# ProPrj_can_sniffer_2026-02-20.net
KiCad netlist of a schematic drawn in EasyEDA Pro
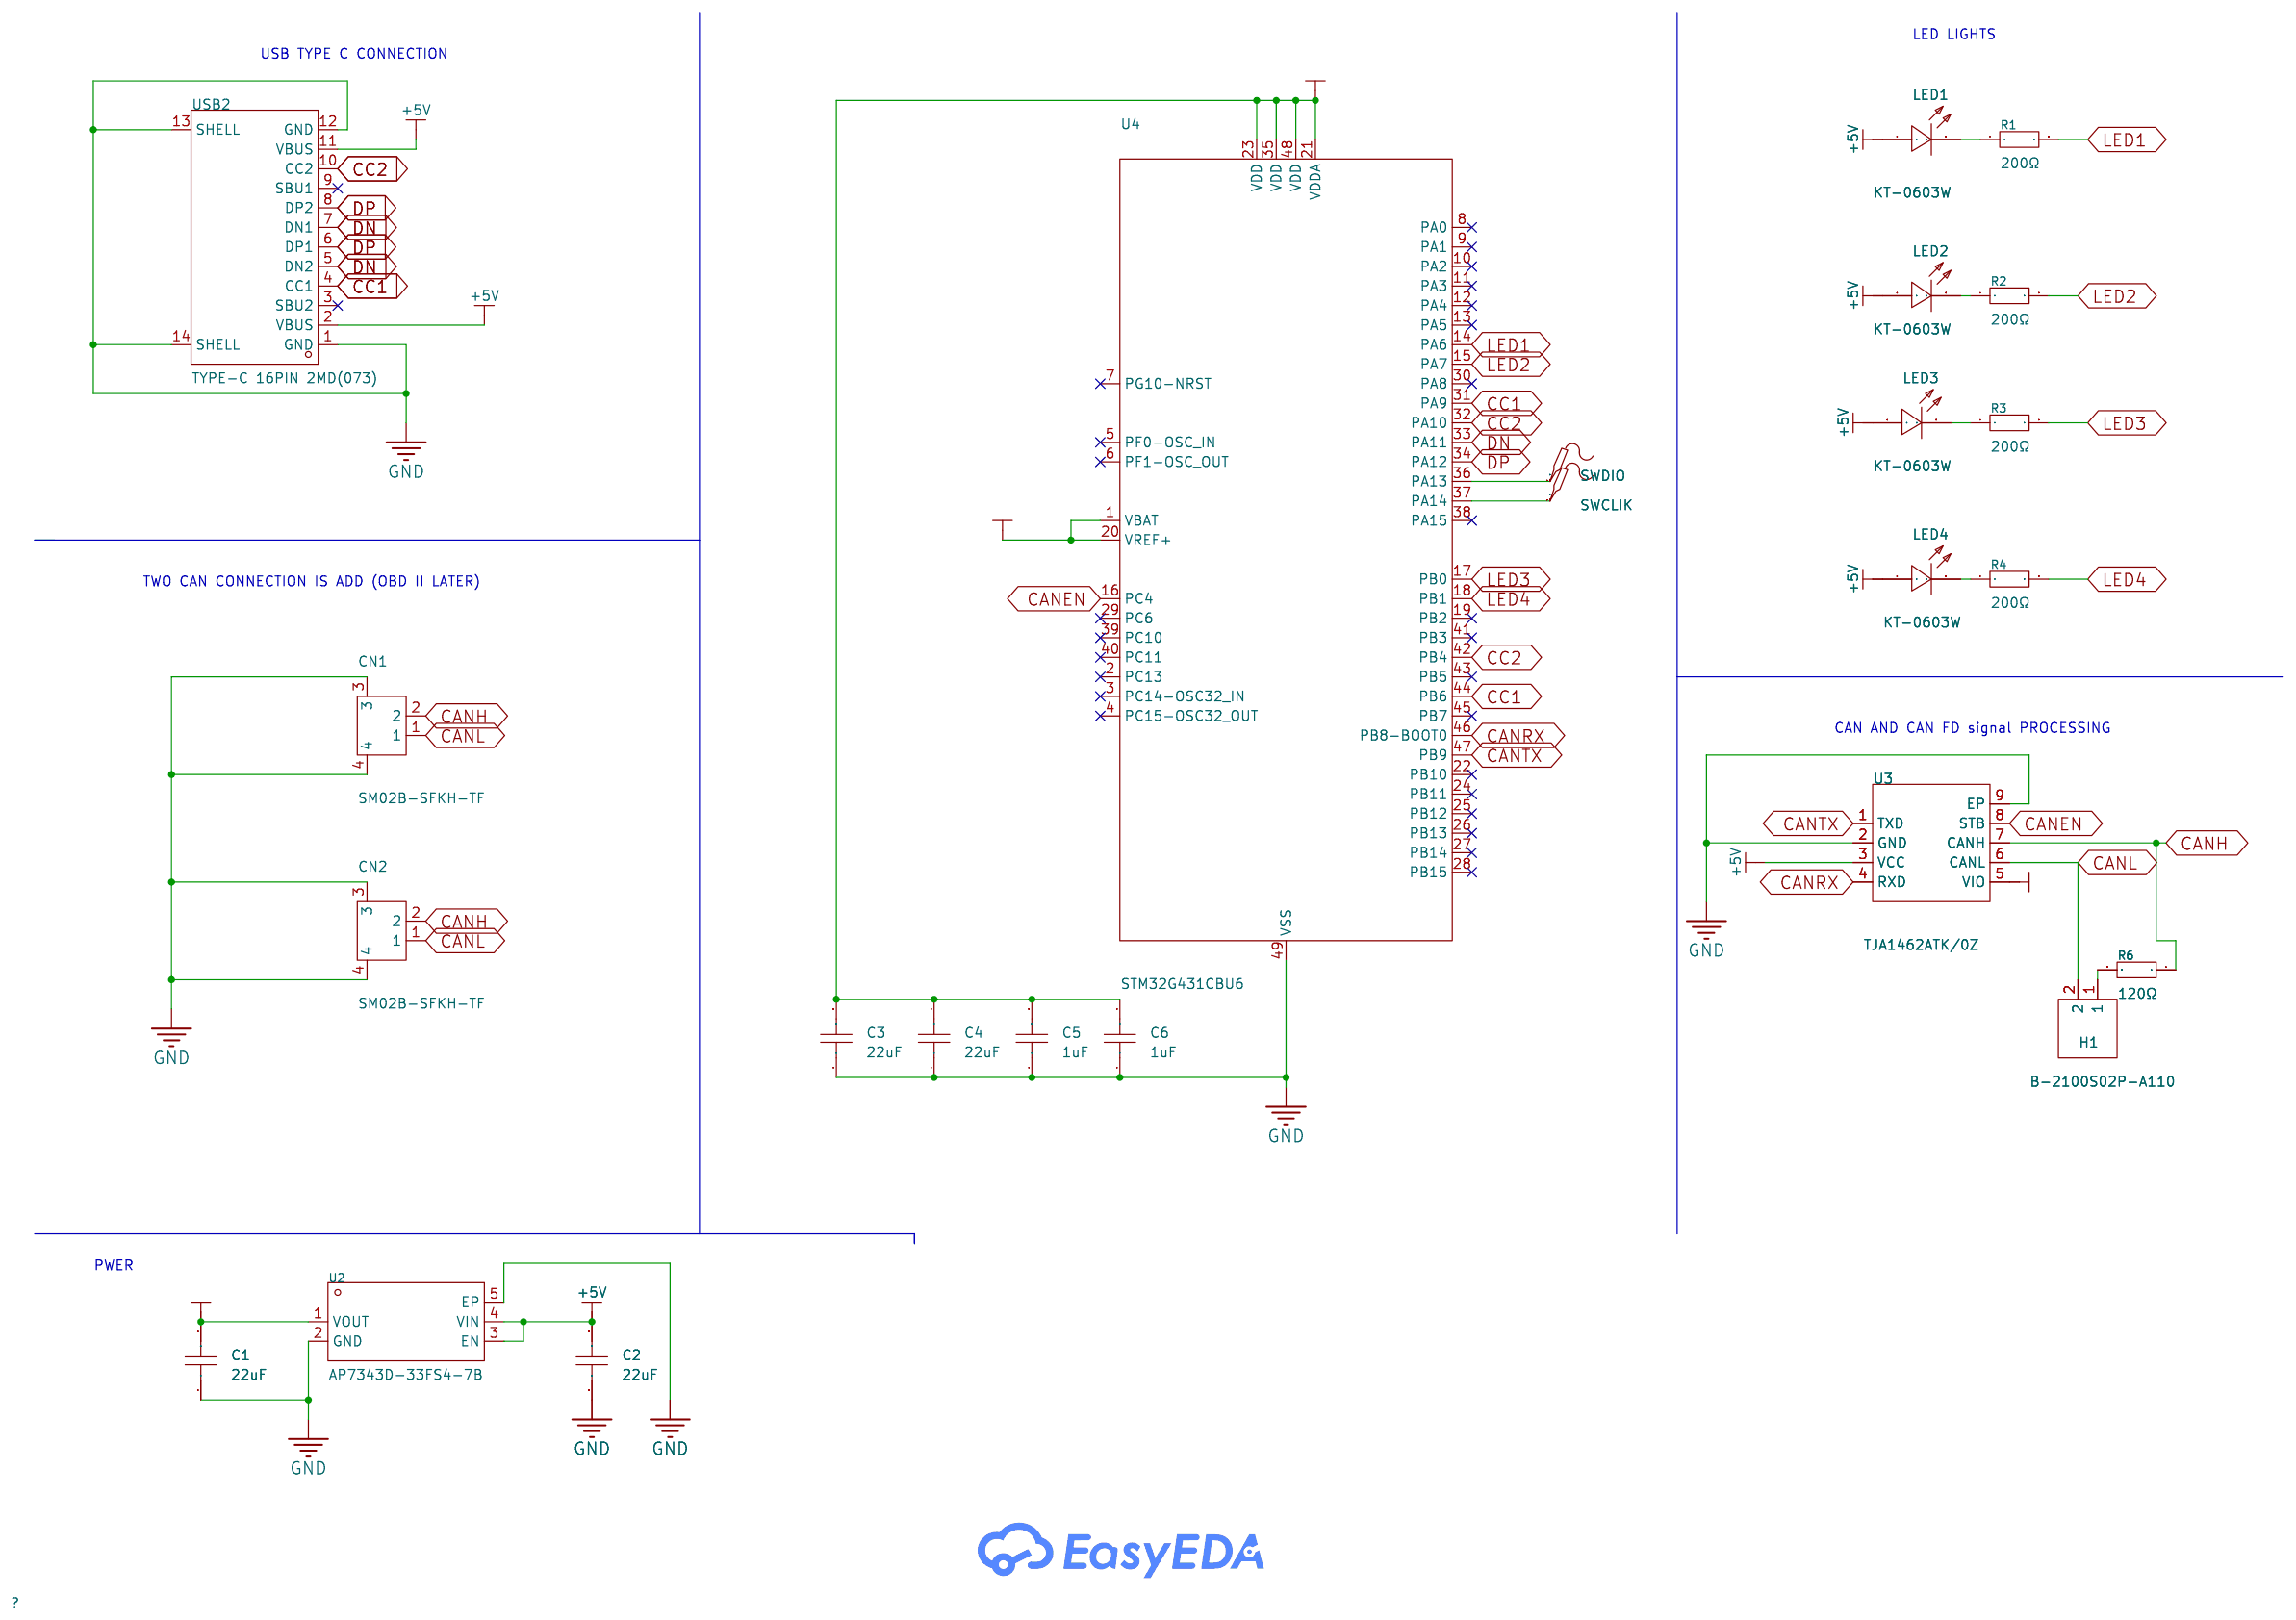
[diagram p0: schematic sheet]

(export (version "E")
  (design (tool "Eeschema 10.0.6"))
  (components
    (comp (ref "C1")
      (value "22uF")
      (footprint "easyedapro:C0603")
      (description "Capacitance:22uF Tolerance:±20% Tolerance:±20% Voltage Rating:6.3V Temperature Coefficient:X5R")
      (fields
        (field (name "Manufacturer Part") "CL10A226MQ8NRNC")
        (field (name "Manufacturer") "SAMSUNG(三星)")
      )
      (libsource (lib "easyedapro") (part "CL10A226MQ8NRNC"))
    )
    (comp (ref "C2")
      (value "22uF")
      (footprint "easyedapro:C0603")
      (description "Capacitance:22uF Tolerance:±20% Tolerance:±20% Voltage Rating:6.3V Temperature Coefficient:X5R")
      (fields
        (field (name "Manufacturer Part") "CL10A226MQ8NRNC")
        (field (name "Manufacturer") "SAMSUNG(三星)")
      )
      (libsource (lib "easyedapro") (part "CL10A226MQ8NRNC"))
    )
    (comp (ref "C3")
      (value "22uF")
      (footprint "easyedapro:C0603")
      (description "Capacitance:22uF Tolerance:±20% Tolerance:±20% Voltage Rating:6.3V Temperature Coefficient:X5R")
      (fields
        (field (name "Manufacturer Part") "CL10A226MQ8NRNC")
        (field (name "Manufacturer") "SAMSUNG(三星)")
      )
      (libsource (lib "easyedapro") (part "CL10A226MQ8NRNC"))
    )
    (comp (ref "C4")
      (value "22uF")
      (footprint "easyedapro:C0603")
      (description "Capacitance:22uF Tolerance:±20% Tolerance:±20% Voltage Rating:6.3V Temperature Coefficient:X5R")
      (fields
        (field (name "Manufacturer Part") "CL10A226MQ8NRNC")
        (field (name "Manufacturer") "SAMSUNG(三星)")
      )
      (libsource (lib "easyedapro") (part "CL10A226MQ8NRNC"))
    )
    (comp (ref "C5")
      (value "1uF")
      (footprint "easyedapro:C0402")
      (description "Capacitance:1uF Tolerance:±10% Tolerance:±10% Voltage Rating:25V Temperature Coefficient:X5R")
      (fields
        (field (name "Manufacturer Part") "CL05A105KA5NQNC")
        (field (name "Manufacturer") "SAMSUNG(三星)")
      )
      (libsource (lib "easyedapro") (part "CL05A105KA5NQNC"))
    )
    (comp (ref "C6")
      (value "1uF")
      (footprint "easyedapro:C0402")
      (description "Capacitance:1uF Tolerance:±10% Tolerance:±10% Voltage Rating:25V Temperature Coefficient:X5R")
      (fields
        (field (name "Manufacturer Part") "CL05A105KA5NQNC")
        (field (name "Manufacturer") "SAMSUNG(三星)")
      )
      (libsource (lib "easyedapro") (part "CL05A105KA5NQNC"))
    )
    (comp (ref "CN1")
      (value "SM02B-SFKH-TF")
      (footprint "easyedapro:CONN-SMD_SM02B-SFKH-TF")
      (fields (field (name "Manufacturer") "JST"))
      (libsource (lib "easyedapro") (part "SM02B-SFKH-TF"))
    )
    (comp (ref "CN2")
      (value "SM02B-SFKH-TF")
      (footprint "easyedapro:CONN-SMD_SM02B-SFKH-TF")
      (fields (field (name "Manufacturer") "JST"))
      (libsource (lib "easyedapro") (part "SM02B-SFKH-TF"))
    )
    (comp (ref "H1")
      (value "B-2100S02P-A110")
      (footprint "easyedapro:HDR-TH_2P-P2.54-V-M-1")
      (fields (field (name "Manufacturer") "Ckmtw(灿科盟)"))
      (libsource (lib "easyedapro") (part "210S-1*2P L=11.6MMGold-plated black"))
    )
    (comp (ref "LED1")
      (value "KT-0603W")
      (footprint "easyedapro:LED0603-R-RD_WHITE")
      (fields (field (name "Manufacturer") "KENTO"))
      (libsource (lib "easyedapro") (part "0603White light_C2290"))
    )
    (comp (ref "LED2")
      (value "KT-0603W")
      (footprint "easyedapro:LED0603-R-RD_WHITE")
      (fields (field (name "Manufacturer") "KENTO"))
      (libsource (lib "easyedapro") (part "0603White light_C2290"))
    )
    (comp (ref "LED3")
      (value "KT-0603W")
      (footprint "easyedapro:LED0603-R-RD_WHITE")
      (fields (field (name "Manufacturer") "KENTO"))
      (libsource (lib "easyedapro") (part "0603White light_C2290"))
    )
    (comp (ref "LED4")
      (value "KT-0603W")
      (footprint "easyedapro:LED0603-R-RD_WHITE")
      (fields (field (name "Manufacturer") "KENTO"))
      (libsource (lib "easyedapro") (part "0603White light_C2290"))
    )
    (comp (ref "R1")
      (value "200Ω")
      (footprint "easyedapro:R0402")
      (fields
        (field (name "Manufacturer Part") "0402WGF2000TCE")
        (field (name "Manufacturer") "UNI-ROYAL(厚声)")
      )
      (libsource (lib "easyedapro") (part "0402WGF2000TCE"))
    )
    (comp (ref "R2")
      (value "200Ω")
      (footprint "easyedapro:R0402")
      (fields
        (field (name "Manufacturer Part") "0402WGF2000TCE")
        (field (name "Manufacturer") "UNI-ROYAL(厚声)")
      )
      (libsource (lib "easyedapro") (part "0402WGF2000TCE"))
    )
    (comp (ref "R3")
      (value "200Ω")
      (footprint "easyedapro:R0402")
      (fields
        (field (name "Manufacturer Part") "0402WGF2000TCE")
        (field (name "Manufacturer") "UNI-ROYAL(厚声)")
      )
      (libsource (lib "easyedapro") (part "0402WGF2000TCE"))
    )
    (comp (ref "R4")
      (value "200Ω")
      (footprint "easyedapro:R0402")
      (fields
        (field (name "Manufacturer Part") "0402WGF2000TCE")
        (field (name "Manufacturer") "UNI-ROYAL(厚声)")
      )
      (libsource (lib "easyedapro") (part "0402WGF2000TCE"))
    )
    (comp (ref "R6")
      (value "120Ω")
      (footprint "easyedapro:R0603")
      (fields
        (field (name "Manufacturer Part") "0603WAF1200T5E")
        (field (name "Manufacturer") "UNI-ROYAL(厚声)")
      )
      (libsource (lib "easyedapro") (part "0603WAF1200T5E"))
    )
    (comp (ref "SWCLIK")
      (value "~")
      (footprint "easyedapro:Test-Point-0.5mm")
      (description "Test Point 测试点")
      (libsource (lib "easyedapro") (part "Test-Point"))
    )
    (comp (ref "SWDIO")
      (value "~")
      (footprint "easyedapro:Test-Point-0.5mm")
      (description "Test Point 测试点")
      (libsource (lib "easyedapro") (part "Test-Point"))
    )
    (comp (ref "U2")
      (value "AP7343D-33FS4-7B")
      (footprint "easyedapro:DFN-4_L1.0-W1.0-P0.65-BL-EP")
      (fields (field (name "Manufacturer") "DIODES(美台)"))
      (libsource (lib "easyedapro") (part "AP7343D-33FS4-7B"))
    )
    (comp (ref "U3")
      (value "TJA1462ATK/0Z")
      (footprint "easyedapro:HVSON-8_L3.0-W3.0-P0.65-TL-EP")
      (fields (field (name "Manufacturer") "NXP(恩智浦)"))
      (libsource (lib "easyedapro") (part "TJA1462ATK/0Z"))
    )
    (comp (ref "U4")
      (value "STM32G431CBU6")
      (footprint "easyedapro:VQFN-48_L7.0-W7.0-P0.50-BL-EP5.5")
      (fields (field (name "Manufacturer") "ST(意法半导体)"))
      (libsource (lib "easyedapro") (part "STM32G431CBU6"))
    )
    (comp (ref "USB2")
      (value "TYPE-C 16PIN 2MD(073)")
      (footprint "easyedapro:USB-C-SMD_TYPE-C-6PIN-2MD-073")
      (fields (field (name "Manufacturer") "SHOU HAN(首韩)"))
      (libsource (lib "easyedapro") (part "TYPE-C 16PIN 2MD(073)"))
    )
  )
  (nets
    (net (code "1") (name "+5V") (class "Default")
      (node (ref "C2") (pin "2") (pinfunction "2_2") (pintype "unspecified"))
      (node (ref "LED1") (pin "1") (pinfunction "A_1") (pintype "unspecified"))
      (node (ref "LED2") (pin "1") (pinfunction "A_1") (pintype "unspecified"))
      (node (ref "LED3") (pin "1") (pinfunction "A_1") (pintype "unspecified"))
      (node (ref "LED4") (pin "1") (pinfunction "A_1") (pintype "unspecified"))
      (node (ref "U2") (pin "3") (pinfunction "EN_3") (pintype "input"))
      (node (ref "U2") (pin "4") (pinfunction "VIN_4") (pintype "input"))
      (node (ref "U3") (pin "3") (pinfunction "VCC_3") (pintype "unspecified"))
      (node (ref "USB2") (pin "11") (pinfunction "VBUS_11") (pintype "unspecified"))
      (node (ref "USB2") (pin "2") (pinfunction "VBUS_2") (pintype "unspecified"))
    )
    (net (code "2") (name "3V3") (class "Default")
      (node (ref "C1") (pin "2") (pinfunction "2_2") (pintype "unspecified"))
      (node (ref "C3") (pin "2") (pinfunction "2_2") (pintype "unspecified"))
      (node (ref "C4") (pin "2") (pinfunction "2_2") (pintype "unspecified"))
      (node (ref "C5") (pin "2") (pinfunction "2_2") (pintype "unspecified"))
      (node (ref "C6") (pin "2") (pinfunction "2_2") (pintype "unspecified"))
      (node (ref "U2") (pin "1") (pinfunction "VOUT_1") (pintype "input"))
      (node (ref "U3") (pin "5") (pinfunction "VIO_5") (pintype "unspecified"))
      (node (ref "U4") (pin "1") (pinfunction "VBAT_1") (pintype "unspecified"))
      (node (ref "U4") (pin "20") (pinfunction "VREF+_20") (pintype "unspecified"))
      (node (ref "U4") (pin "21") (pinfunction "VDDA_21") (pintype "unspecified"))
      (node (ref "U4") (pin "23") (pinfunction "VDD_23") (pintype "unspecified"))
      (node (ref "U4") (pin "35") (pinfunction "VDD_35") (pintype "unspecified"))
      (node (ref "U4") (pin "48") (pinfunction "VDD_48") (pintype "unspecified"))
    )
    (net (code "3") (name "CANEN") (class "Default")
      (node (ref "U3") (pin "8") (pinfunction "STB_8") (pintype "unspecified"))
      (node (ref "U4") (pin "16") (pinfunction "PC4_16") (pintype "unspecified"))
    )
    (net (code "4") (name "CANH") (class "Default")
      (node (ref "CN1") (pin "2") (pinfunction "2_2") (pintype "unspecified"))
      (node (ref "CN2") (pin "2") (pinfunction "2_2") (pintype "unspecified"))
      (node (ref "R6") (pin "1") (pinfunction "1_1") (pintype "input"))
      (node (ref "U3") (pin "7") (pinfunction "CANH_7") (pintype "unspecified"))
    )
    (net (code "5") (name "CANL") (class "Default")
      (node (ref "CN1") (pin "1") (pinfunction "1_1") (pintype "unspecified"))
      (node (ref "CN2") (pin "1") (pinfunction "1_1") (pintype "unspecified"))
      (node (ref "H1") (pin "2") (pinfunction "2_2") (pintype "unspecified"))
      (node (ref "U3") (pin "6") (pinfunction "CANL_6") (pintype "unspecified"))
    )
    (net (code "6") (name "CANRX") (class "Default")
      (node (ref "U3") (pin "4") (pinfunction "RXD_4") (pintype "unspecified"))
      (node (ref "U4") (pin "46") (pinfunction "PB8-BOOT0_46") (pintype "unspecified"))
    )
    (net (code "7") (name "CANTX") (class "Default")
      (node (ref "U3") (pin "1") (pinfunction "TXD_1") (pintype "unspecified"))
      (node (ref "U4") (pin "47") (pinfunction "PB9_47") (pintype "unspecified"))
    )
    (net (code "8") (name "CC1") (class "Default")
      (node (ref "U4") (pin "31") (pinfunction "PA9_31") (pintype "unspecified"))
      (node (ref "U4") (pin "44") (pinfunction "PB6_44") (pintype "unspecified"))
      (node (ref "USB2") (pin "4") (pinfunction "CC1_4") (pintype "unspecified"))
    )
    (net (code "9") (name "CC2") (class "Default")
      (node (ref "U4") (pin "32") (pinfunction "PA10_32") (pintype "unspecified"))
      (node (ref "U4") (pin "42") (pinfunction "PB4_42") (pintype "unspecified"))
      (node (ref "USB2") (pin "10") (pinfunction "CC2_10") (pintype "unspecified"))
    )
    (net (code "10") (name "DN") (class "Default")
      (node (ref "U4") (pin "33") (pinfunction "PA11_33") (pintype "unspecified"))
      (node (ref "USB2") (pin "5") (pinfunction "DN2_5") (pintype "unspecified"))
      (node (ref "USB2") (pin "7") (pinfunction "DN1_7") (pintype "unspecified"))
    )
    (net (code "11") (name "DP") (class "Default")
      (node (ref "U4") (pin "34") (pinfunction "PA12_34") (pintype "unspecified"))
      (node (ref "USB2") (pin "6") (pinfunction "DP1_6") (pintype "unspecified"))
      (node (ref "USB2") (pin "8") (pinfunction "DP2_8") (pintype "unspecified"))
    )
    (net (code "12") (name "GND") (class "Default")
      (node (ref "C1") (pin "1") (pinfunction "1_1") (pintype "unspecified"))
      (node (ref "C2") (pin "1") (pinfunction "1_1") (pintype "unspecified"))
      (node (ref "C3") (pin "1") (pinfunction "1_1") (pintype "unspecified"))
      (node (ref "C4") (pin "1") (pinfunction "1_1") (pintype "unspecified"))
      (node (ref "C5") (pin "1") (pinfunction "1_1") (pintype "unspecified"))
      (node (ref "C6") (pin "1") (pinfunction "1_1") (pintype "unspecified"))
      (node (ref "CN1") (pin "3") (pinfunction "3_3") (pintype "unspecified"))
      (node (ref "CN1") (pin "4") (pinfunction "4_4") (pintype "unspecified"))
      (node (ref "CN2") (pin "3") (pinfunction "3_3") (pintype "unspecified"))
      (node (ref "CN2") (pin "4") (pinfunction "4_4") (pintype "unspecified"))
      (node (ref "U2") (pin "2") (pinfunction "GND_2") (pintype "input"))
      (node (ref "U2") (pin "5") (pinfunction "EP_5") (pintype "input"))
      (node (ref "U3") (pin "2") (pinfunction "GND_2") (pintype "unspecified"))
      (node (ref "U3") (pin "9") (pinfunction "EP_9") (pintype "unspecified"))
      (node (ref "U4") (pin "49") (pinfunction "VSS_49") (pintype "unspecified"))
      (node (ref "USB2") (pin "1") (pinfunction "GND_1") (pintype "unspecified"))
      (node (ref "USB2") (pin "12") (pinfunction "GND_12") (pintype "unspecified"))
      (node (ref "USB2") (pin "13") (pinfunction "SHELL_13") (pintype "unspecified"))
      (node (ref "USB2") (pin "14") (pinfunction "SHELL_14") (pintype "unspecified"))
    )
    (net (code "13") (name "LED1") (class "Default")
      (node (ref "R1") (pin "2") (pinfunction "2_2") (pintype "input"))
      (node (ref "U4") (pin "14") (pinfunction "PA6_14") (pintype "unspecified"))
    )
    (net (code "14") (name "LED2") (class "Default")
      (node (ref "R2") (pin "2") (pinfunction "2_2") (pintype "input"))
      (node (ref "U4") (pin "15") (pinfunction "PA7_15") (pintype "unspecified"))
    )
    (net (code "15") (name "LED3") (class "Default")
      (node (ref "R3") (pin "2") (pinfunction "2_2") (pintype "input"))
      (node (ref "U4") (pin "17") (pinfunction "PB0_17") (pintype "unspecified"))
    )
    (net (code "16") (name "LED4") (class "Default")
      (node (ref "R4") (pin "2") (pinfunction "2_2") (pintype "input"))
      (node (ref "U4") (pin "18") (pinfunction "PB1_18") (pintype "unspecified"))
    )
    (net (code "17") (name "Net-(H1-Pad1)") (class "Default")
      (node (ref "H1") (pin "1") (pinfunction "1_1") (pintype "unspecified"))
      (node (ref "R6") (pin "2") (pinfunction "2_2") (pintype "input"))
    )
    (net (code "18") (name "Net-(LED1-K)") (class "Default")
      (node (ref "LED1") (pin "2") (pinfunction "K_2") (pintype "unspecified"))
      (node (ref "R1") (pin "1") (pinfunction "1_1") (pintype "input"))
    )
    (net (code "19") (name "Net-(LED2-K)") (class "Default")
      (node (ref "LED2") (pin "2") (pinfunction "K_2") (pintype "unspecified"))
      (node (ref "R2") (pin "1") (pinfunction "1_1") (pintype "input"))
    )
    (net (code "20") (name "Net-(LED3-K)") (class "Default")
      (node (ref "LED3") (pin "2") (pinfunction "K_2") (pintype "unspecified"))
      (node (ref "R3") (pin "1") (pinfunction "1_1") (pintype "input"))
    )
    (net (code "21") (name "Net-(LED4-K)") (class "Default")
      (node (ref "LED4") (pin "2") (pinfunction "K_2") (pintype "unspecified"))
      (node (ref "R4") (pin "1") (pinfunction "1_1") (pintype "input"))
    )
    (net (code "22") (name "Net-(U4-PA13)") (class "Default")
      (node (ref "SWDIO") (pin "1") (pinfunction "1_1") (pintype "unspecified"))
      (node (ref "U4") (pin "36") (pinfunction "PA13_36") (pintype "unspecified"))
    )
    (net (code "23") (name "Net-(U4-PA14)") (class "Default")
      (node (ref "SWCLIK") (pin "1") (pinfunction "1_1") (pintype "unspecified"))
      (node (ref "U4") (pin "37") (pinfunction "PA14_37") (pintype "unspecified"))
    )
    (net (code "24") (name "unconnected-(U4-PA0-Pad8)") (class "Default")
      (node (ref "U4") (pin "8") (pinfunction "PA0_8") (pintype "unspecified+no_connect"))
    )
    (net (code "25") (name "unconnected-(U4-PA1-Pad9)") (class "Default")
      (node (ref "U4") (pin "9") (pinfunction "PA1_9") (pintype "unspecified+no_connect"))
    )
    (net (code "26") (name "unconnected-(U4-PA2-Pad10)") (class "Default")
      (node (ref "U4") (pin "10") (pinfunction "PA2_10") (pintype "unspecified+no_connect"))
    )
    (net (code "27") (name "unconnected-(U4-PA3-Pad11)") (class "Default")
      (node (ref "U4") (pin "11") (pinfunction "PA3_11") (pintype "unspecified+no_connect"))
    )
    (net (code "28") (name "unconnected-(U4-PA4-Pad12)") (class "Default")
      (node (ref "U4") (pin "12") (pinfunction "PA4_12") (pintype "unspecified+no_connect"))
    )
    (net (code "29") (name "unconnected-(U4-PA5-Pad13)") (class "Default")
      (node (ref "U4") (pin "13") (pinfunction "PA5_13") (pintype "unspecified+no_connect"))
    )
    (net (code "30") (name "unconnected-(U4-PA8-Pad30)") (class "Default")
      (node (ref "U4") (pin "30") (pinfunction "PA8_30") (pintype "unspecified+no_connect"))
    )
    (net (code "31") (name "unconnected-(U4-PA15-Pad38)") (class "Default")
      (node (ref "U4") (pin "38") (pinfunction "PA15_38") (pintype "unspecified+no_connect"))
    )
    (net (code "32") (name "unconnected-(U4-PB2-Pad19)") (class "Default")
      (node (ref "U4") (pin "19") (pinfunction "PB2_19") (pintype "unspecified+no_connect"))
    )
    (net (code "33") (name "unconnected-(U4-PB3-Pad41)") (class "Default")
      (node (ref "U4") (pin "41") (pinfunction "PB3_41") (pintype "unspecified+no_connect"))
    )
    (net (code "34") (name "unconnected-(U4-PB5-Pad43)") (class "Default")
      (node (ref "U4") (pin "43") (pinfunction "PB5_43") (pintype "unspecified+no_connect"))
    )
    (net (code "35") (name "unconnected-(U4-PB7-Pad45)") (class "Default")
      (node (ref "U4") (pin "45") (pinfunction "PB7_45") (pintype "unspecified+no_connect"))
    )
    (net (code "36") (name "unconnected-(U4-PB10-Pad22)") (class "Default")
      (node (ref "U4") (pin "22") (pinfunction "PB10_22") (pintype "unspecified+no_connect"))
    )
    (net (code "37") (name "unconnected-(U4-PB11-Pad24)") (class "Default")
      (node (ref "U4") (pin "24") (pinfunction "PB11_24") (pintype "unspecified+no_connect"))
    )
    (net (code "38") (name "unconnected-(U4-PB12-Pad25)") (class "Default")
      (node (ref "U4") (pin "25") (pinfunction "PB12_25") (pintype "unspecified+no_connect"))
    )
    (net (code "39") (name "unconnected-(U4-PB13-Pad26)") (class "Default")
      (node (ref "U4") (pin "26") (pinfunction "PB13_26") (pintype "unspecified+no_connect"))
    )
    (net (code "40") (name "unconnected-(U4-PB14-Pad27)") (class "Default")
      (node (ref "U4") (pin "27") (pinfunction "PB14_27") (pintype "unspecified+no_connect"))
    )
    (net (code "41") (name "unconnected-(U4-PB15-Pad28)") (class "Default")
      (node (ref "U4") (pin "28") (pinfunction "PB15_28") (pintype "unspecified+no_connect"))
    )
    (net (code "42") (name "unconnected-(U4-PC6-Pad29)") (class "Default")
      (node (ref "U4") (pin "29") (pinfunction "PC6_29") (pintype "unspecified+no_connect"))
    )
    (net (code "43") (name "unconnected-(U4-PC10-Pad39)") (class "Default")
      (node (ref "U4") (pin "39") (pinfunction "PC10_39") (pintype "unspecified+no_connect"))
    )
    (net (code "44") (name "unconnected-(U4-PC11-Pad40)") (class "Default")
      (node (ref "U4") (pin "40") (pinfunction "PC11_40") (pintype "unspecified+no_connect"))
    )
    (net (code "45") (name "unconnected-(U4-PC13-Pad2)") (class "Default")
      (node (ref "U4") (pin "2") (pinfunction "PC13_2") (pintype "unspecified+no_connect"))
    )
    (net (code "46") (name "unconnected-(U4-PC14-OSC32_IN-Pad3)") (class "Default")
      (node (ref "U4") (pin "3") (pinfunction "PC14-OSC32_IN_3") (pintype "unspecified+no_connect"))
    )
    (net (code "47") (name "unconnected-(U4-PC15-OSC32_OUT-Pad4)") (class "Default")
      (node (ref "U4") (pin "4") (pinfunction "PC15-OSC32_OUT_4") (pintype "unspecified+no_connect"))
    )
    (net (code "48") (name "unconnected-(U4-PF0-OSC_IN-Pad5)") (class "Default")
      (node (ref "U4") (pin "5") (pinfunction "PF0-OSC_IN_5") (pintype "unspecified+no_connect"))
    )
    (net (code "49") (name "unconnected-(U4-PF1-OSC_OUT-Pad6)") (class "Default")
      (node (ref "U4") (pin "6") (pinfunction "PF1-OSC_OUT_6") (pintype "unspecified+no_connect"))
    )
    (net (code "50") (name "unconnected-(U4-PG10-NRST-Pad7)") (class "Default")
      (node (ref "U4") (pin "7") (pinfunction "PG10-NRST_7") (pintype "unspecified+no_connect"))
    )
    (net (code "51") (name "unconnected-(USB2-SBU1-Pad9)") (class "Default")
      (node (ref "USB2") (pin "9") (pinfunction "SBU1_9") (pintype "unspecified+no_connect"))
    )
    (net (code "52") (name "unconnected-(USB2-SBU2-Pad3)") (class "Default")
      (node (ref "USB2") (pin "3") (pinfunction "SBU2_3") (pintype "unspecified+no_connect"))
    )
  )
)
